# 07_LMS7002M_Power.net
KiCad netlist of a schematic drawn in Altium Designer
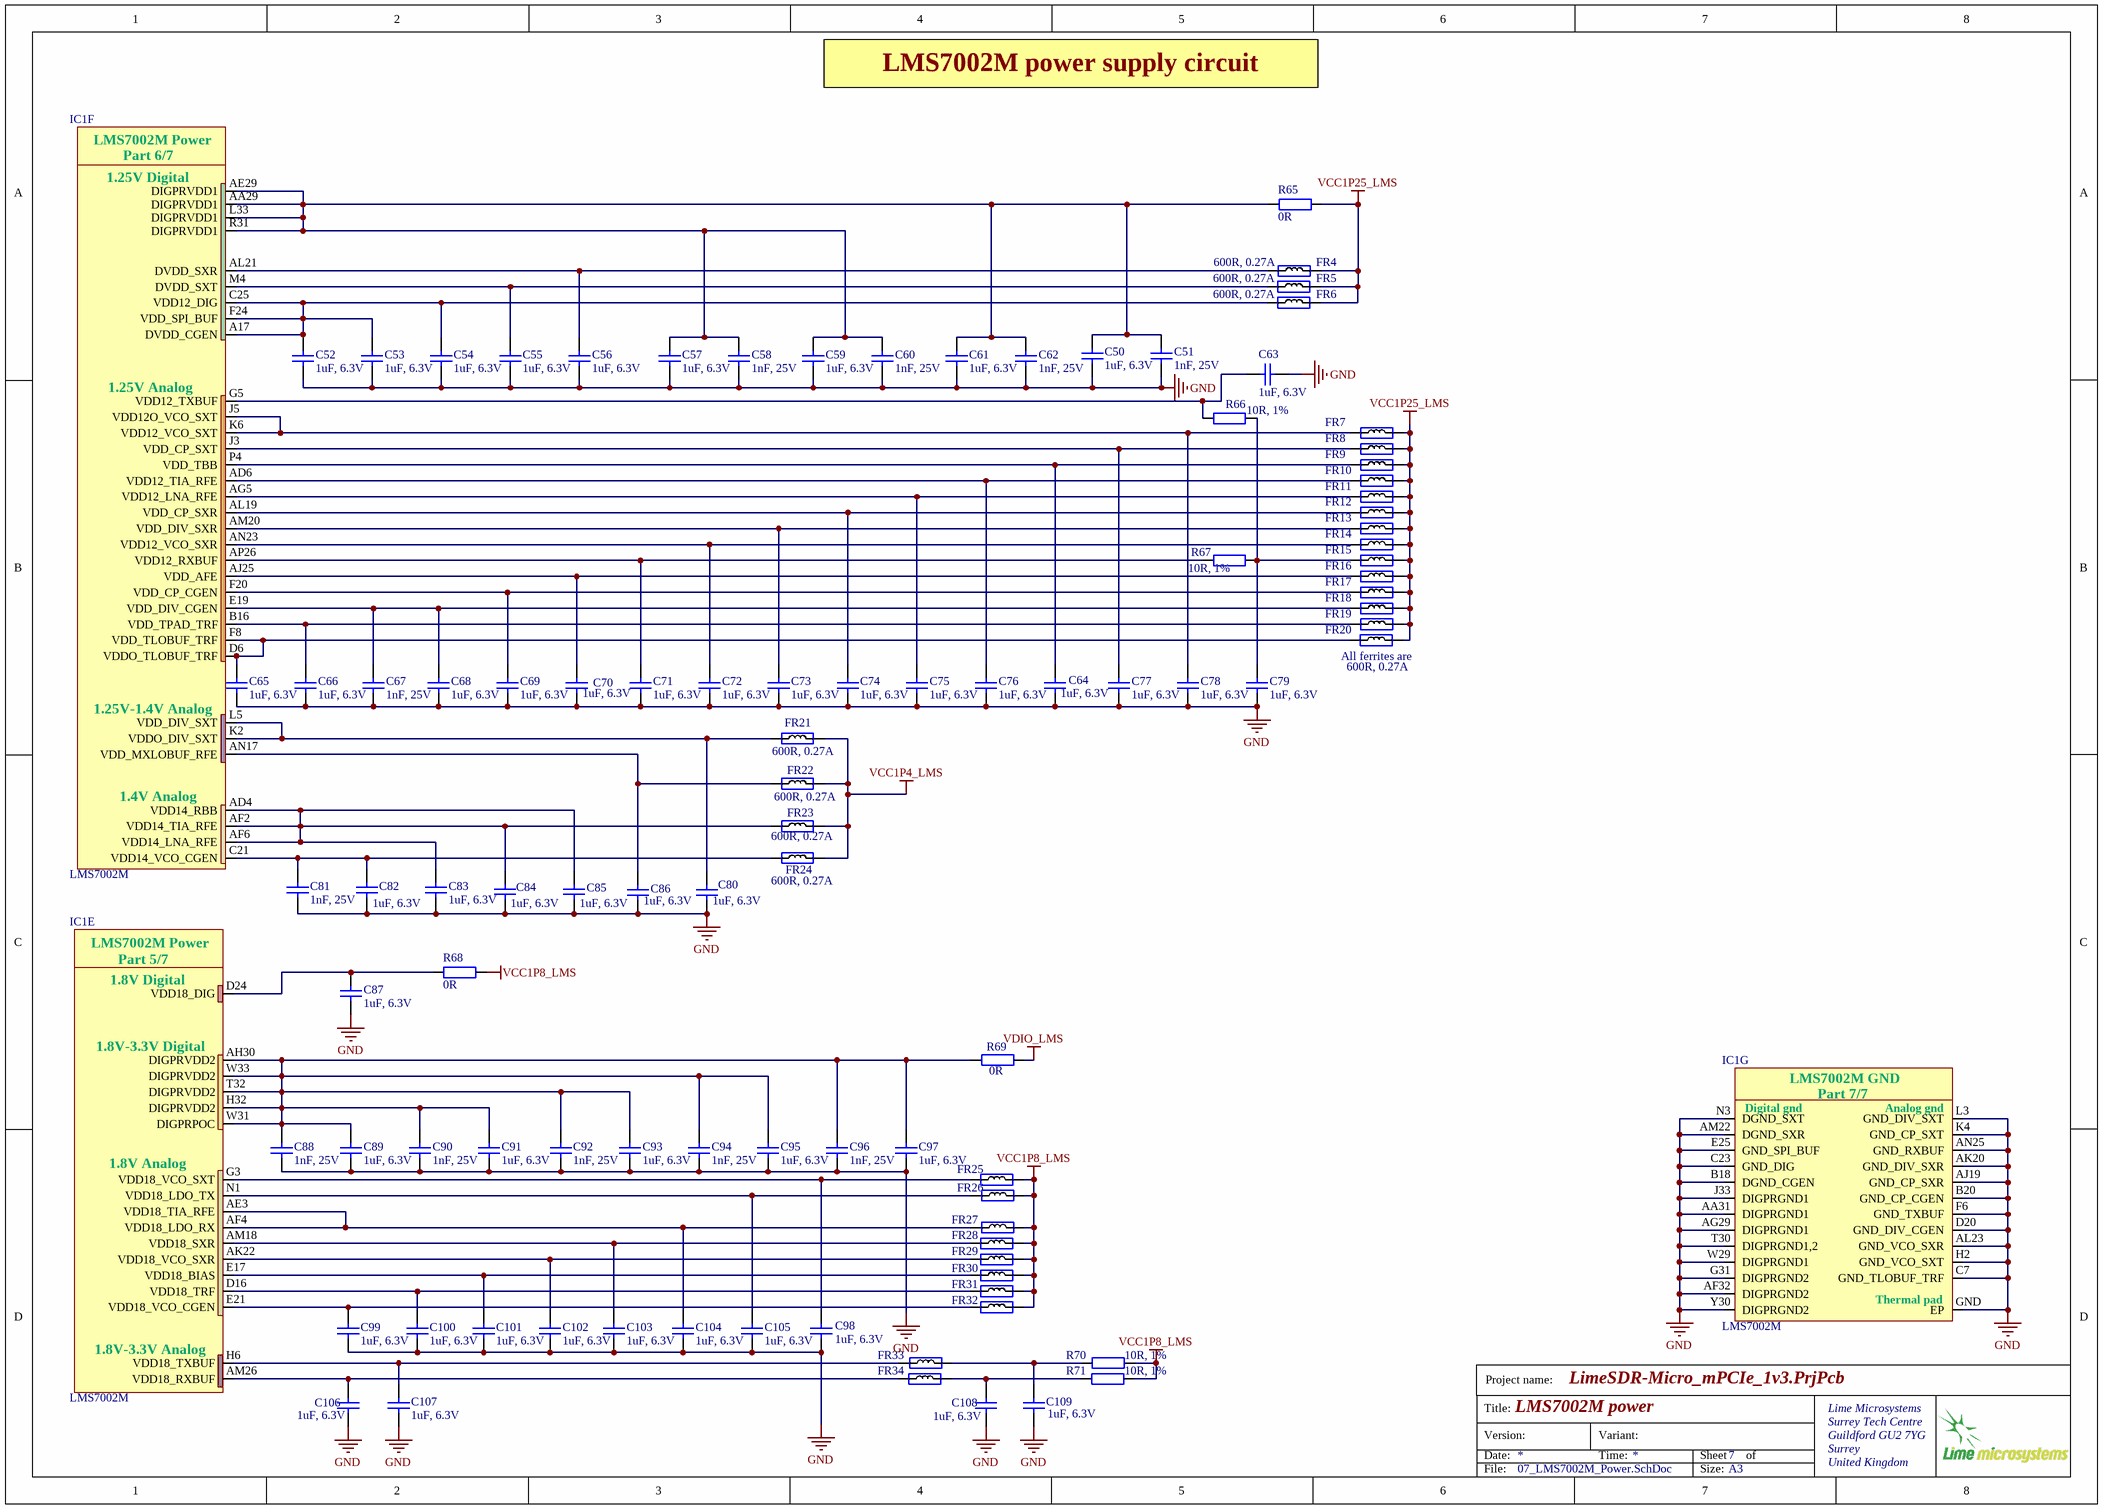
[diagram p0: 07_LMS7002M_Power.SchDoc]

(export (version "E")
  (design (tool "Eeschema 10.0.6"))
  (components
    (comp (ref "C50")
      (value "1uF, 6.3V")
      (footprint "CAP0201")
      (fields (field (name "TOLERANCE") "±20%") (field (name "MANUFACTURER") "TDK Corporation"))
      (libsource (lib "LimeMicroAltiumLib_schLib") (part "Cap_0402"))
    )
    (comp (ref "C51")
      (value "1nF, 25V")
      (footprint "CAP0201")
      (fields (field (name "TOLERANCE") "±10%") (field (name "MANUFACTURER") "TDK Corporation"))
      (libsource (lib "LimeMicroAltiumLib_schLib") (part "Cap_0402"))
    )
    (comp (ref "C52")
      (value "1uF, 6.3V")
      (footprint "CAP0201")
      (fields (field (name "TOLERANCE") "±20%") (field (name "MANUFACTURER") "TDK Corporation"))
      (libsource (lib "LimeMicroAltiumLib_schLib") (part "Cap_0402"))
    )
    (comp (ref "C53")
      (value "1uF, 6.3V")
      (footprint "CAP0201")
      (fields (field (name "TOLERANCE") "±20%") (field (name "MANUFACTURER") "TDK Corporation"))
      (libsource (lib "LimeMicroAltiumLib_schLib") (part "Cap_0402"))
    )
    (comp (ref "C54")
      (value "1uF, 6.3V")
      (footprint "CAP0201")
      (fields (field (name "TOLERANCE") "±20%") (field (name "MANUFACTURER") "TDK Corporation"))
      (libsource (lib "LimeMicroAltiumLib_schLib") (part "Cap_0402"))
    )
    (comp (ref "C55")
      (value "1uF, 6.3V")
      (footprint "CAP0201")
      (fields (field (name "TOLERANCE") "±20%") (field (name "MANUFACTURER") "TDK Corporation"))
      (libsource (lib "LimeMicroAltiumLib_schLib") (part "Cap_0402"))
    )
    (comp (ref "C56")
      (value "1uF, 6.3V")
      (footprint "CAP0201")
      (fields (field (name "TOLERANCE") "±20%") (field (name "MANUFACTURER") "TDK Corporation"))
      (libsource (lib "LimeMicroAltiumLib_schLib") (part "Cap_0402"))
    )
    (comp (ref "C57")
      (value "1uF, 6.3V")
      (footprint "CAP0201")
      (fields (field (name "TOLERANCE") "±20%") (field (name "MANUFACTURER") "TDK Corporation"))
      (libsource (lib "LimeMicroAltiumLib_schLib") (part "Cap_0402"))
    )
    (comp (ref "C58")
      (value "1nF, 25V")
      (footprint "CAP0201")
      (fields (field (name "TOLERANCE") "±10%") (field (name "MANUFACTURER") "TDK Corporation"))
      (libsource (lib "LimeMicroAltiumLib_schLib") (part "Cap_0402"))
    )
    (comp (ref "C59")
      (value "1uF, 6.3V")
      (footprint "CAP0201")
      (fields (field (name "TOLERANCE") "±20%") (field (name "MANUFACTURER") "TDK Corporation"))
      (libsource (lib "LimeMicroAltiumLib_schLib") (part "Cap_0402"))
    )
    (comp (ref "C60")
      (value "1nF, 25V")
      (footprint "CAP0201")
      (fields (field (name "TOLERANCE") "±10%") (field (name "MANUFACTURER") "TDK Corporation"))
      (libsource (lib "LimeMicroAltiumLib_schLib") (part "Cap_0402"))
    )
    (comp (ref "C61")
      (value "1uF, 6.3V")
      (footprint "CAP0201")
      (fields (field (name "TOLERANCE") "±20%") (field (name "MANUFACTURER") "TDK Corporation"))
      (libsource (lib "LimeMicroAltiumLib_schLib") (part "Cap_0402"))
    )
    (comp (ref "C62")
      (value "1nF, 25V")
      (footprint "CAP0201")
      (fields (field (name "TOLERANCE") "±10%") (field (name "MANUFACTURER") "TDK Corporation"))
      (libsource (lib "LimeMicroAltiumLib_schLib") (part "Cap_0402"))
    )
    (comp (ref "C63")
      (value "1uF, 6.3V")
      (footprint "CAP0201")
      (fields (field (name "TOLERANCE") "±20%") (field (name "MANUFACTURER") "TDK Corporation"))
      (libsource (lib "LimeMicroAltiumLib_schLib") (part "Cap_0402"))
    )
    (comp (ref "C64")
      (value "1uF, 6.3V")
      (footprint "CAP0201")
      (fields (field (name "TOLERANCE") "±20%") (field (name "MANUFACTURER") "TDK Corporation"))
      (libsource (lib "LimeMicroAltiumLib_schLib") (part "Cap_0402"))
    )
    (comp (ref "C65")
      (value "1uF, 6.3V")
      (footprint "CAP0201")
      (fields (field (name "TOLERANCE") "±20%") (field (name "MANUFACTURER") "TDK Corporation"))
      (libsource (lib "LimeMicroAltiumLib_schLib") (part "Cap_0402"))
    )
    (comp (ref "C66")
      (value "1uF, 6.3V")
      (footprint "CAP0201")
      (fields (field (name "TOLERANCE") "±20%") (field (name "MANUFACTURER") "TDK Corporation"))
      (libsource (lib "LimeMicroAltiumLib_schLib") (part "Cap_0402"))
    )
    (comp (ref "C67")
      (value "1nF, 25V")
      (footprint "CAP0201")
      (fields (field (name "TOLERANCE") "±10%") (field (name "MANUFACTURER") "TDK Corporation"))
      (libsource (lib "LimeMicroAltiumLib_schLib") (part "Cap_0402"))
    )
    (comp (ref "C68")
      (value "1uF, 6.3V")
      (footprint "CAP0201")
      (fields (field (name "TOLERANCE") "±20%") (field (name "MANUFACTURER") "TDK Corporation"))
      (libsource (lib "LimeMicroAltiumLib_schLib") (part "Cap_0402"))
    )
    (comp (ref "C69")
      (value "1uF, 6.3V")
      (footprint "CAP0201")
      (fields (field (name "TOLERANCE") "±20%") (field (name "MANUFACTURER") "TDK Corporation"))
      (libsource (lib "LimeMicroAltiumLib_schLib") (part "Cap_0402"))
    )
    (comp (ref "C70")
      (value "1uF, 6.3V")
      (footprint "CAP0201")
      (fields (field (name "TOLERANCE") "±20%") (field (name "MANUFACTURER") "TDK Corporation"))
      (libsource (lib "LimeMicroAltiumLib_schLib") (part "Cap_0402"))
    )
    (comp (ref "C71")
      (value "1uF, 6.3V")
      (footprint "CAP0201")
      (fields (field (name "TOLERANCE") "±20%") (field (name "MANUFACTURER") "TDK Corporation"))
      (libsource (lib "LimeMicroAltiumLib_schLib") (part "Cap_0402"))
    )
    (comp (ref "C72")
      (value "1uF, 6.3V")
      (footprint "CAP0201")
      (fields (field (name "TOLERANCE") "±20%") (field (name "MANUFACTURER") "TDK Corporation"))
      (libsource (lib "LimeMicroAltiumLib_schLib") (part "Cap_0402"))
    )
    (comp (ref "C73")
      (value "1uF, 6.3V")
      (footprint "CAP0201")
      (fields (field (name "TOLERANCE") "±20%") (field (name "MANUFACTURER") "TDK Corporation"))
      (libsource (lib "LimeMicroAltiumLib_schLib") (part "Cap_0402"))
    )
    (comp (ref "C74")
      (value "1uF, 6.3V")
      (footprint "CAP0201")
      (fields (field (name "TOLERANCE") "±20%") (field (name "MANUFACTURER") "TDK Corporation"))
      (libsource (lib "LimeMicroAltiumLib_schLib") (part "Cap_0402"))
    )
    (comp (ref "C75")
      (value "1uF, 6.3V")
      (footprint "CAP0201")
      (fields (field (name "TOLERANCE") "±20%") (field (name "MANUFACTURER") "TDK Corporation"))
      (libsource (lib "LimeMicroAltiumLib_schLib") (part "Cap_0402"))
    )
    (comp (ref "C76")
      (value "1uF, 6.3V")
      (footprint "CAP0201")
      (fields (field (name "TOLERANCE") "±20%") (field (name "MANUFACTURER") "TDK Corporation"))
      (libsource (lib "LimeMicroAltiumLib_schLib") (part "Cap_0402"))
    )
    (comp (ref "C77")
      (value "1uF, 6.3V")
      (footprint "CAP0201")
      (fields (field (name "TOLERANCE") "±20%") (field (name "MANUFACTURER") "TDK Corporation"))
      (libsource (lib "LimeMicroAltiumLib_schLib") (part "Cap_0402"))
    )
    (comp (ref "C78")
      (value "1uF, 6.3V")
      (footprint "CAP0201")
      (fields (field (name "TOLERANCE") "±20%") (field (name "MANUFACTURER") "TDK Corporation"))
      (libsource (lib "LimeMicroAltiumLib_schLib") (part "Cap_0402"))
    )
    (comp (ref "C79")
      (value "1uF, 6.3V")
      (footprint "CAP0201")
      (fields (field (name "TOLERANCE") "±20%") (field (name "MANUFACTURER") "TDK Corporation"))
      (libsource (lib "LimeMicroAltiumLib_schLib") (part "Cap_0402"))
    )
    (comp (ref "C80")
      (value "1uF, 6.3V")
      (footprint "CAP0201")
      (fields (field (name "TOLERANCE") "±20%") (field (name "MANUFACTURER") "TDK Corporation"))
      (libsource (lib "LimeMicroAltiumLib_schLib") (part "Cap_0402"))
    )
    (comp (ref "C81")
      (value "1nF, 25V")
      (footprint "CAP0201")
      (fields (field (name "TOLERANCE") "±10%") (field (name "MANUFACTURER") "TDK Corporation"))
      (libsource (lib "LimeMicroAltiumLib_schLib") (part "Cap_0402"))
    )
    (comp (ref "C82")
      (value "1uF, 6.3V")
      (footprint "CAP0201")
      (fields (field (name "TOLERANCE") "±20%") (field (name "MANUFACTURER") "TDK Corporation"))
      (libsource (lib "LimeMicroAltiumLib_schLib") (part "Cap_0402"))
    )
    (comp (ref "C83")
      (value "1uF, 6.3V")
      (footprint "CAP0201")
      (fields (field (name "TOLERANCE") "±20%") (field (name "MANUFACTURER") "TDK Corporation"))
      (libsource (lib "LimeMicroAltiumLib_schLib") (part "Cap_0402"))
    )
    (comp (ref "C84")
      (value "1uF, 6.3V")
      (footprint "CAP0201")
      (fields (field (name "TOLERANCE") "±20%") (field (name "MANUFACTURER") "TDK Corporation"))
      (libsource (lib "LimeMicroAltiumLib_schLib") (part "Cap_0402"))
    )
    (comp (ref "C85")
      (value "1uF, 6.3V")
      (footprint "CAP0201")
      (fields (field (name "TOLERANCE") "±20%") (field (name "MANUFACTURER") "TDK Corporation"))
      (libsource (lib "LimeMicroAltiumLib_schLib") (part "Cap_0402"))
    )
    (comp (ref "C86")
      (value "1uF, 6.3V")
      (footprint "CAP0201")
      (fields (field (name "TOLERANCE") "±20%") (field (name "MANUFACTURER") "TDK Corporation"))
      (libsource (lib "LimeMicroAltiumLib_schLib") (part "Cap_0402"))
    )
    (comp (ref "C87")
      (value "1uF, 6.3V")
      (footprint "CAP0201")
      (fields (field (name "TOLERANCE") "±20%") (field (name "MANUFACTURER") "TDK Corporation"))
      (libsource (lib "LimeMicroAltiumLib_schLib") (part "Cap_0402"))
    )
    (comp (ref "C88")
      (value "1nF, 25V")
      (footprint "CAP0201")
      (fields (field (name "TOLERANCE") "±10%") (field (name "MANUFACTURER") "TDK Corporation"))
      (libsource (lib "LimeMicroAltiumLib_schLib") (part "Cap_0402"))
    )
    (comp (ref "C89")
      (value "1uF, 6.3V")
      (footprint "CAP0201")
      (fields (field (name "TOLERANCE") "±20%") (field (name "MANUFACTURER") "TDK Corporation"))
      (libsource (lib "LimeMicroAltiumLib_schLib") (part "Cap_0402"))
    )
    (comp (ref "C90")
      (value "1nF, 25V")
      (footprint "CAP0201")
      (fields (field (name "TOLERANCE") "±10%") (field (name "MANUFACTURER") "TDK Corporation"))
      (libsource (lib "LimeMicroAltiumLib_schLib") (part "Cap_0402"))
    )
    (comp (ref "C91")
      (value "1uF, 6.3V")
      (footprint "CAP0201")
      (fields (field (name "TOLERANCE") "±20%") (field (name "MANUFACTURER") "TDK Corporation"))
      (libsource (lib "LimeMicroAltiumLib_schLib") (part "Cap_0402"))
    )
    (comp (ref "C92")
      (value "1nF, 25V")
      (footprint "CAP0201")
      (fields (field (name "TOLERANCE") "±10%") (field (name "MANUFACTURER") "TDK Corporation"))
      (libsource (lib "LimeMicroAltiumLib_schLib") (part "Cap_0402"))
    )
    (comp (ref "C93")
      (value "1uF, 6.3V")
      (footprint "CAP0201")
      (fields (field (name "TOLERANCE") "±20%") (field (name "MANUFACTURER") "TDK Corporation"))
      (libsource (lib "LimeMicroAltiumLib_schLib") (part "Cap_0402"))
    )
    (comp (ref "C94")
      (value "1nF, 25V")
      (footprint "CAP0201")
      (fields (field (name "TOLERANCE") "±10%") (field (name "MANUFACTURER") "TDK Corporation"))
      (libsource (lib "LimeMicroAltiumLib_schLib") (part "Cap_0402"))
    )
    (comp (ref "C95")
      (value "1uF, 6.3V")
      (footprint "CAP0201")
      (fields (field (name "TOLERANCE") "±20%") (field (name "MANUFACTURER") "TDK Corporation"))
      (libsource (lib "LimeMicroAltiumLib_schLib") (part "Cap_0402"))
    )
    (comp (ref "C96")
      (value "1nF, 25V")
      (footprint "CAP0201")
      (fields (field (name "TOLERANCE") "±10%") (field (name "MANUFACTURER") "TDK Corporation"))
      (libsource (lib "LimeMicroAltiumLib_schLib") (part "Cap_0402"))
    )
    (comp (ref "C97")
      (value "1uF, 6.3V")
      (footprint "CAP0201")
      (fields (field (name "TOLERANCE") "±20%") (field (name "MANUFACTURER") "TDK Corporation"))
      (libsource (lib "LimeMicroAltiumLib_schLib") (part "Cap_0402"))
    )
    (comp (ref "C98")
      (value "1uF, 6.3V")
      (footprint "CAP0201")
      (fields (field (name "TOLERANCE") "±20%") (field (name "MANUFACTURER") "TDK Corporation"))
      (libsource (lib "LimeMicroAltiumLib_schLib") (part "Cap_0402"))
    )
    (comp (ref "C99")
      (value "1uF, 6.3V")
      (footprint "CAP0201")
      (fields (field (name "TOLERANCE") "±20%") (field (name "MANUFACTURER") "TDK Corporation"))
      (libsource (lib "LimeMicroAltiumLib_schLib") (part "Cap_0402"))
    )
    (comp (ref "C100")
      (value "1uF, 6.3V")
      (footprint "CAP0201")
      (fields (field (name "TOLERANCE") "±20%") (field (name "MANUFACTURER") "TDK Corporation"))
      (libsource (lib "LimeMicroAltiumLib_schLib") (part "Cap_0402"))
    )
    (comp (ref "C101")
      (value "1uF, 6.3V")
      (footprint "CAP0201")
      (fields (field (name "TOLERANCE") "±20%") (field (name "MANUFACTURER") "TDK Corporation"))
      (libsource (lib "LimeMicroAltiumLib_schLib") (part "Cap_0402"))
    )
    (comp (ref "C102")
      (value "1uF, 6.3V")
      (footprint "CAP0201")
      (fields (field (name "TOLERANCE") "±20%") (field (name "MANUFACTURER") "TDK Corporation"))
      (libsource (lib "LimeMicroAltiumLib_schLib") (part "Cap_0402"))
    )
    (comp (ref "C103")
      (value "1uF, 6.3V")
      (footprint "CAP0201")
      (fields (field (name "TOLERANCE") "±20%") (field (name "MANUFACTURER") "TDK Corporation"))
      (libsource (lib "LimeMicroAltiumLib_schLib") (part "Cap_0402"))
    )
    (comp (ref "C104")
      (value "1uF, 6.3V")
      (footprint "CAP0201")
      (fields (field (name "TOLERANCE") "±20%") (field (name "MANUFACTURER") "TDK Corporation"))
      (libsource (lib "LimeMicroAltiumLib_schLib") (part "Cap_0402"))
    )
    (comp (ref "C105")
      (value "1uF, 6.3V")
      (footprint "CAP0201")
      (fields (field (name "TOLERANCE") "±20%") (field (name "MANUFACTURER") "TDK Corporation"))
      (libsource (lib "LimeMicroAltiumLib_schLib") (part "Cap_0402"))
    )
    (comp (ref "C106")
      (value "1uF, 6.3V")
      (footprint "CAP0201")
      (fields (field (name "TOLERANCE") "±20%") (field (name "MANUFACTURER") "TDK Corporation"))
      (libsource (lib "LimeMicroAltiumLib_schLib") (part "Cap_0402"))
    )
    (comp (ref "C107")
      (value "1uF, 6.3V")
      (footprint "CAP0201")
      (fields (field (name "TOLERANCE") "±20%") (field (name "MANUFACTURER") "TDK Corporation"))
      (libsource (lib "LimeMicroAltiumLib_schLib") (part "Cap_0402"))
    )
    (comp (ref "C108")
      (value "1uF, 6.3V")
      (footprint "CAP0201")
      (fields (field (name "TOLERANCE") "±20%") (field (name "MANUFACTURER") "TDK Corporation"))
      (libsource (lib "LimeMicroAltiumLib_schLib") (part "Cap_0402"))
    )
    (comp (ref "C109")
      (value "1uF, 6.3V")
      (footprint "CAP0201")
      (fields (field (name "TOLERANCE") "±20%") (field (name "MANUFACTURER") "TDK Corporation"))
      (libsource (lib "LimeMicroAltiumLib_schLib") (part "Cap_0402"))
    )
    (comp (ref "FR4")
      (value "600R, 0.27A")
      (footprint "RES0201")
      (fields (field (name "MANUFACTURER") "Taiyo Yuden"))
      (libsource (lib "LimeMicroAltiumLib_schLib") (part "Ferrite"))
    )
    (comp (ref "FR5")
      (value "600R, 0.27A")
      (footprint "RES0201")
      (fields (field (name "MANUFACTURER") "Taiyo Yuden"))
      (libsource (lib "LimeMicroAltiumLib_schLib") (part "Ferrite"))
    )
    (comp (ref "FR6")
      (value "600R, 0.27A")
      (footprint "RES0201")
      (fields (field (name "MANUFACTURER") "Taiyo Yuden"))
      (libsource (lib "LimeMicroAltiumLib_schLib") (part "Ferrite"))
    )
    (comp (ref "FR7")
      (value "600R, 0.27A")
      (footprint "RES0201")
      (fields (field (name "MANUFACTURER") "Taiyo Yuden"))
      (libsource (lib "LimeMicroAltiumLib_schLib") (part "Ferrite"))
    )
    (comp (ref "FR8")
      (value "600R, 0.27A")
      (footprint "RES0201")
      (fields (field (name "MANUFACTURER") "Taiyo Yuden"))
      (libsource (lib "LimeMicroAltiumLib_schLib") (part "Ferrite"))
    )
    (comp (ref "FR9")
      (value "600R, 0.27A")
      (footprint "RES0201")
      (fields (field (name "MANUFACTURER") "Taiyo Yuden"))
      (libsource (lib "LimeMicroAltiumLib_schLib") (part "Ferrite"))
    )
    (comp (ref "FR10")
      (value "600R, 0.27A")
      (footprint "RES0201")
      (fields (field (name "MANUFACTURER") "Taiyo Yuden"))
      (libsource (lib "LimeMicroAltiumLib_schLib") (part "Ferrite"))
    )
    (comp (ref "FR11")
      (value "600R, 0.27A")
      (footprint "RES0201")
      (fields (field (name "MANUFACTURER") "Taiyo Yuden"))
      (libsource (lib "LimeMicroAltiumLib_schLib") (part "Ferrite"))
    )
    (comp (ref "FR12")
      (value "600R, 0.27A")
      (footprint "RES0201")
      (fields (field (name "MANUFACTURER") "Taiyo Yuden"))
      (libsource (lib "LimeMicroAltiumLib_schLib") (part "Ferrite"))
    )
    (comp (ref "FR13")
      (value "600R, 0.27A")
      (footprint "RES0201")
      (fields (field (name "MANUFACTURER") "Taiyo Yuden"))
      (libsource (lib "LimeMicroAltiumLib_schLib") (part "Ferrite"))
    )
    (comp (ref "FR14")
      (value "600R, 0.27A")
      (footprint "RES0201")
      (fields (field (name "MANUFACTURER") "Taiyo Yuden"))
      (libsource (lib "LimeMicroAltiumLib_schLib") (part "Ferrite"))
    )
    (comp (ref "FR15")
      (value "600R, 0.27A")
      (footprint "RES0201")
      (fields (field (name "MANUFACTURER") "Taiyo Yuden"))
      (libsource (lib "LimeMicroAltiumLib_schLib") (part "Ferrite"))
    )
    (comp (ref "FR16")
      (value "600R, 0.27A")
      (footprint "RES0201")
      (fields (field (name "MANUFACTURER") "Taiyo Yuden"))
      (libsource (lib "LimeMicroAltiumLib_schLib") (part "Ferrite"))
    )
    (comp (ref "FR17")
      (value "600R, 0.27A")
      (footprint "RES0201")
      (fields (field (name "MANUFACTURER") "Taiyo Yuden"))
      (libsource (lib "LimeMicroAltiumLib_schLib") (part "Ferrite"))
    )
    (comp (ref "FR18")
      (value "600R, 0.27A")
      (footprint "RES0201")
      (fields (field (name "MANUFACTURER") "Taiyo Yuden"))
      (libsource (lib "LimeMicroAltiumLib_schLib") (part "Ferrite"))
    )
    (comp (ref "FR19")
      (value "600R, 0.27A")
      (footprint "RES0201")
      (fields (field (name "MANUFACTURER") "Taiyo Yuden"))
      (libsource (lib "LimeMicroAltiumLib_schLib") (part "Ferrite"))
    )
    (comp (ref "FR20")
      (value "600R, 0.27A")
      (footprint "RES0201")
      (fields (field (name "MANUFACTURER") "Taiyo Yuden"))
      (libsource (lib "LimeMicroAltiumLib_schLib") (part "Ferrite"))
    )
    (comp (ref "FR21")
      (value "600R, 0.27A")
      (footprint "RES0201")
      (fields (field (name "MANUFACTURER") "Taiyo Yuden"))
      (libsource (lib "LimeMicroAltiumLib_schLib") (part "Ferrite"))
    )
    (comp (ref "FR22")
      (value "600R, 0.27A")
      (footprint "RES0201")
      (fields (field (name "MANUFACTURER") "Taiyo Yuden"))
      (libsource (lib "LimeMicroAltiumLib_schLib") (part "Ferrite"))
    )
    (comp (ref "FR23")
      (value "600R, 0.27A")
      (footprint "RES0201")
      (fields (field (name "MANUFACTURER") "Taiyo Yuden"))
      (libsource (lib "LimeMicroAltiumLib_schLib") (part "Ferrite"))
    )
    (comp (ref "FR24")
      (value "600R, 0.27A")
      (footprint "RES0201")
      (fields (field (name "MANUFACTURER") "Taiyo Yuden"))
      (libsource (lib "LimeMicroAltiumLib_schLib") (part "Ferrite"))
    )
    (comp (ref "FR25")
      (value "600R, 0.27A")
      (footprint "RES0201")
      (fields (field (name "MANUFACTURER") "Taiyo Yuden"))
      (libsource (lib "LimeMicroAltiumLib_schLib") (part "Ferrite"))
    )
    (comp (ref "FR26")
      (value "600R, 0.27A")
      (footprint "RES0201")
      (fields (field (name "MANUFACTURER") "Taiyo Yuden"))
      (libsource (lib "") (part "Ferrite_1"))
    )
    (comp (ref "FR27")
      (value "600R, 0.27A")
      (footprint "RES0201")
      (fields (field (name "MANUFACTURER") "Taiyo Yuden"))
      (libsource (lib "") (part "Ferrite_1"))
    )
    (comp (ref "FR28")
      (value "600R, 0.27A")
      (footprint "RES0201")
      (fields (field (name "MANUFACTURER") "Taiyo Yuden"))
      (libsource (lib "LimeMicroAltiumLib_schLib") (part "Ferrite"))
    )
    (comp (ref "FR29")
      (value "600R, 0.27A")
      (footprint "RES0201")
      (fields (field (name "MANUFACTURER") "Taiyo Yuden"))
      (libsource (lib "LimeMicroAltiumLib_schLib") (part "Ferrite"))
    )
    (comp (ref "FR30")
      (value "600R, 0.27A")
      (footprint "RES0201")
      (fields (field (name "MANUFACTURER") "Taiyo Yuden"))
      (libsource (lib "LimeMicroAltiumLib_schLib") (part "Ferrite"))
    )
    (comp (ref "FR31")
      (value "600R, 0.27A")
      (footprint "RES0201")
      (fields (field (name "MANUFACTURER") "Taiyo Yuden"))
      (libsource (lib "LimeMicroAltiumLib_schLib") (part "Ferrite"))
    )
    (comp (ref "FR32")
      (value "600R, 0.27A")
      (footprint "RES0201")
      (fields (field (name "MANUFACTURER") "Taiyo Yuden"))
      (libsource (lib "LimeMicroAltiumLib_schLib") (part "Ferrite"))
    )
    (comp (ref "FR33")
      (value "600R, 0.27A")
      (footprint "RES0201")
      (fields (field (name "MANUFACTURER") "Taiyo Yuden"))
      (libsource (lib "") (part "Ferrite_1"))
    )
    (comp (ref "FR34")
      (value "600R, 0.27A")
      (footprint "RES0201")
      (fields (field (name "MANUFACTURER") "Taiyo Yuden"))
      (libsource (lib "LimeMicroAltiumLib_schLib") (part "Ferrite"))
    )
    (comp (ref "IC1")
      (value "LMS7002M")
      (footprint "LMS7002M_v5_LESS_SILK")
      (description "Schematic symbol revision 4. Default footprint - 0.31mm pad")
      (fields (field (name "MANUFACTURER") "Lime Microsystems"))
      (libsource (lib "LimeMicroAltiumLib_schLib_r04") (part "LMS7002Mr4"))
    )
    (comp (ref "R65")
      (value "0R")
      (footprint "RES0402")
      (fields (field (name "MANUFACTURER") "Yageo") (field (name "TOLERANCE") "Jumper"))
      (libsource (lib "LimeMicroAltiumLib_schLib") (part "Res_0402"))
    )
    (comp (ref "R66")
      (value "10R, 1%")
      (footprint "RES0201")
      (fields
        (field (name "MANUFACTURER") "Panasonic Electronic Components")
        (field (name "TOLERANCE") "±1%")
      )
      (libsource (lib "LimeMicroAltiumLib_schLib") (part "Res_0402"))
    )
    (comp (ref "R67")
      (value "10R, 1%")
      (footprint "RES0201")
      (fields
        (field (name "MANUFACTURER") "Panasonic Electronic Components")
        (field (name "TOLERANCE") "±1%")
      )
      (libsource (lib "LimeMicroAltiumLib_schLib") (part "Res_0402"))
    )
    (comp (ref "R68")
      (value "0R")
      (footprint "RES0201")
      (fields (field (name "MANUFACTURER") "Yageo") (field (name "TOLERANCE") "5%"))
      (libsource (lib "LimeMicroAltiumLib_schLib") (part "Res_0402"))
    )
    (comp (ref "R69")
      (value "0R")
      (footprint "RES0402")
      (fields (field (name "MANUFACTURER") "Yageo") (field (name "TOLERANCE") "Jumper"))
      (libsource (lib "LimeMicroAltiumLib_schLib") (part "Res_0402"))
    )
    (comp (ref "R70")
      (value "10R, 1%")
      (footprint "RES0201")
      (fields
        (field (name "MANUFACTURER") "Panasonic Electronic Components")
        (field (name "TOLERANCE") "±1%")
      )
      (libsource (lib "LimeMicroAltiumLib_schLib") (part "Res_0402"))
    )
    (comp (ref "R71")
      (value "10R, 1%")
      (footprint "RES0201")
      (fields
        (field (name "MANUFACTURER") "Panasonic Electronic Components")
        (field (name "TOLERANCE") "±1%")
      )
      (libsource (lib "LimeMicroAltiumLib_schLib") (part "Res_0402"))
    )
  )
  (nets
    (net (code "1") (name "GND") (class "Default")
      (node (ref "C100") (pin "2") (pinfunction "2_2") (pintype "passive"))
      (node (ref "C101") (pin "2") (pinfunction "2_2") (pintype "passive"))
      (node (ref "C102") (pin "2") (pinfunction "2_2") (pintype "passive"))
      (node (ref "C103") (pin "2") (pinfunction "2_2") (pintype "passive"))
      (node (ref "C104") (pin "2") (pinfunction "2_2") (pintype "passive"))
      (node (ref "C105") (pin "2") (pinfunction "2_2") (pintype "passive"))
      (node (ref "C106") (pin "2") (pinfunction "2_2") (pintype "passive"))
      (node (ref "C107") (pin "2") (pinfunction "2_2") (pintype "passive"))
      (node (ref "C108") (pin "2") (pinfunction "2_2") (pintype "passive"))
      (node (ref "C109") (pin "2") (pinfunction "2_2") (pintype "passive"))
      (node (ref "C50") (pin "2") (pinfunction "2_2") (pintype "passive"))
      (node (ref "C51") (pin "2") (pinfunction "2_2") (pintype "passive"))
      (node (ref "C52") (pin "2") (pinfunction "2_2") (pintype "passive"))
      (node (ref "C53") (pin "2") (pinfunction "2_2") (pintype "passive"))
      (node (ref "C54") (pin "2") (pinfunction "2_2") (pintype "passive"))
      (node (ref "C55") (pin "1") (pinfunction "1_1") (pintype "passive"))
      (node (ref "C56") (pin "2") (pinfunction "2_2") (pintype "passive"))
      (node (ref "C57") (pin "2") (pinfunction "2_2") (pintype "passive"))
      (node (ref "C58") (pin "2") (pinfunction "2_2") (pintype "passive"))
      (node (ref "C59") (pin "2") (pinfunction "2_2") (pintype "passive"))
      (node (ref "C60") (pin "2") (pinfunction "2_2") (pintype "passive"))
      (node (ref "C61") (pin "2") (pinfunction "2_2") (pintype "passive"))
      (node (ref "C62") (pin "2") (pinfunction "2_2") (pintype "passive"))
      (node (ref "C63") (pin "2") (pinfunction "2_2") (pintype "passive"))
      (node (ref "C64") (pin "2") (pinfunction "2_2") (pintype "passive"))
      (node (ref "C65") (pin "2") (pinfunction "2_2") (pintype "passive"))
      (node (ref "C66") (pin "2") (pinfunction "2_2") (pintype "passive"))
      (node (ref "C67") (pin "2") (pinfunction "2_2") (pintype "passive"))
      (node (ref "C68") (pin "2") (pinfunction "2_2") (pintype "passive"))
      (node (ref "C69") (pin "1") (pinfunction "1_1") (pintype "passive"))
      (node (ref "C70") (pin "2") (pinfunction "2_2") (pintype "passive"))
      (node (ref "C71") (pin "2") (pinfunction "2_2") (pintype "passive"))
      (node (ref "C72") (pin "2") (pinfunction "2_2") (pintype "passive"))
      (node (ref "C73") (pin "2") (pinfunction "2_2") (pintype "passive"))
      (node (ref "C74") (pin "2") (pinfunction "2_2") (pintype "passive"))
      (node (ref "C75") (pin "2") (pinfunction "2_2") (pintype "passive"))
      (node (ref "C76") (pin "1") (pinfunction "1_1") (pintype "passive"))
      (node (ref "C77") (pin "2") (pinfunction "2_2") (pintype "passive"))
      (node (ref "C78") (pin "1") (pinfunction "1_1") (pintype "passive"))
      (node (ref "C79") (pin "1") (pinfunction "1_1") (pintype "passive"))
      (node (ref "C80") (pin "2") (pinfunction "2_2") (pintype "passive"))
      (node (ref "C81") (pin "2") (pinfunction "2_2") (pintype "passive"))
      (node (ref "C82") (pin "2") (pinfunction "2_2") (pintype "passive"))
      (node (ref "C83") (pin "2") (pinfunction "2_2") (pintype "passive"))
      (node (ref "C84") (pin "2") (pinfunction "2_2") (pintype "passive"))
      (node (ref "C85") (pin "2") (pinfunction "2_2") (pintype "passive"))
      (node (ref "C86") (pin "2") (pinfunction "2_2") (pintype "passive"))
      (node (ref "C87") (pin "2") (pinfunction "2_2") (pintype "passive"))
      (node (ref "C88") (pin "2") (pinfunction "2_2") (pintype "passive"))
      (node (ref "C89") (pin "2") (pinfunction "2_2") (pintype "passive"))
      (node (ref "C90") (pin "2") (pinfunction "2_2") (pintype "passive"))
      (node (ref "C91") (pin "2") (pinfunction "2_2") (pintype "passive"))
      (node (ref "C92") (pin "2") (pinfunction "2_2") (pintype "passive"))
      (node (ref "C93") (pin "2") (pinfunction "2_2") (pintype "passive"))
      (node (ref "C94") (pin "2") (pinfunction "2_2") (pintype "passive"))
      (node (ref "C95") (pin "2") (pinfunction "2_2") (pintype "passive"))
      (node (ref "C96") (pin "2") (pinfunction "2_2") (pintype "passive"))
      (node (ref "C97") (pin "2") (pinfunction "2_2") (pintype "passive"))
      (node (ref "C98") (pin "2") (pinfunction "2_2") (pintype "passive"))
      (node (ref "C99") (pin "2") (pinfunction "2_2") (pintype "passive"))
      (node (ref "IC1") (pin "AA31") (pinfunction "DIGPRGND1_AA31") (pintype "passive"))
      (node (ref "IC1") (pin "AF32") (pinfunction "DIGPRGND2_AF32") (pintype "passive"))
      (node (ref "IC1") (pin "AG29") (pinfunction "DIGPRGND1_AG29") (pintype "passive"))
      (node (ref "IC1") (pin "AJ19") (pinfunction "GND_CP_SXR_AJ19") (pintype "passive"))
      (node (ref "IC1") (pin "AK20") (pinfunction "GND_DIV_SXR_AK20") (pintype "passive"))
      (node (ref "IC1") (pin "AL23") (pinfunction "GND_VCO_SXR_AL23") (pintype "passive"))
      (node (ref "IC1") (pin "AM22") (pinfunction "DGND_SXR_AM22") (pintype "passive"))
      (node (ref "IC1") (pin "AN25") (pinfunction "GND_RXBUF_AN25") (pintype "passive"))
      (node (ref "IC1") (pin "B18") (pinfunction "DGND_CGEN_B18") (pintype "passive"))
      (node (ref "IC1") (pin "B20") (pinfunction "GND_CP_CGEN_B20") (pintype "passive"))
      (node (ref "IC1") (pin "C23") (pinfunction "GND_DIG_C23") (pintype "passive"))
      (node (ref "IC1") (pin "C7") (pinfunction "GND_TLOBUF_TRF_C7") (pintype "passive"))
      (node (ref "IC1") (pin "D20") (pinfunction "GND_DIV_CGEN_D20") (pintype "passive"))
      (node (ref "IC1") (pin "E25") (pinfunction "GND_SPI_BUF_E25") (pintype "passive"))
      (node (ref "IC1") (pin "F6") (pinfunction "GND_TXBUF_F6") (pintype "passive"))
      (node (ref "IC1") (pin "G31") (pinfunction "DIGPRGND2_G31") (pintype "passive"))
      (node (ref "IC1") (pin "GND") (pinfunction "EP_GND") (pintype "passive"))
      (node (ref "IC1") (pin "H2") (pinfunction "GND_VCO_SXT_H2") (pintype "passive"))
      (node (ref "IC1") (pin "J33") (pinfunction "DIGPRGND1_J33") (pintype "passive"))
      (node (ref "IC1") (pin "K4") (pinfunction "GND_CP_SXT_K4") (pintype "passive"))
      (node (ref "IC1") (pin "L3") (pinfunction "GND_DIV_SXT_L3") (pintype "passive"))
      (node (ref "IC1") (pin "N3") (pinfunction "DGND_SXT_N3") (pintype "passive"))
      (node (ref "IC1") (pin "T30") (pinfunction "DIGPRGND1,2_T30") (pintype "passive"))
      (node (ref "IC1") (pin "W29") (pinfunction "DIGPRGND1_W29") (pintype "passive"))
      (node (ref "IC1") (pin "Y30") (pinfunction "DIGPRGND2_Y30") (pintype "passive"))
    )
    (net (code "2") (name "Net-(C50-Pad1)") (class "Default")
      (node (ref "C50") (pin "1") (pinfunction "1_1") (pintype "passive"))
      (node (ref "C51") (pin "1") (pinfunction "1_1") (pintype "passive"))
      (node (ref "C57") (pin "1") (pinfunction "1_1") (pintype "passive"))
      (node (ref "C58") (pin "1") (pinfunction "1_1") (pintype "passive"))
      (node (ref "C59") (pin "1") (pinfunction "1_1") (pintype "passive"))
      (node (ref "C60") (pin "1") (pinfunction "1_1") (pintype "passive"))
      (node (ref "C61") (pin "1") (pinfunction "1_1") (pintype "passive"))
      (node (ref "C62") (pin "1") (pinfunction "1_1") (pintype "passive"))
      (node (ref "IC1") (pin "AA29") (pinfunction "DIGPRVDD1_AA29") (pintype "power_in"))
      (node (ref "IC1") (pin "AE29") (pinfunction "DIGPRVDD1_AE29") (pintype "power_in"))
      (node (ref "IC1") (pin "L33") (pinfunction "DIGPRVDD1_L33") (pintype "power_in"))
      (node (ref "IC1") (pin "R31") (pinfunction "DIGPRVDD1_R31") (pintype "power_in"))
      (node (ref "R65") (pin "2") (pinfunction "2_2") (pintype "passive"))
    )
    (net (code "3") (name "Net-(C79-Pad2)") (class "Default")
      (node (ref "C79") (pin "2") (pinfunction "2_2") (pintype "passive"))
      (node (ref "FR15") (pin "1") (pinfunction "1_1") (pintype "passive"))
      (node (ref "R66") (pin "2") (pinfunction "2_2") (pintype "passive"))
      (node (ref "R67") (pin "2") (pinfunction "2_2") (pintype "passive"))
    )
    (net (code "4") (name "Net-(C108-Pad1)") (class "Default")
      (node (ref "C108") (pin "1") (pinfunction "1_1") (pintype "passive"))
      (node (ref "FR34") (pin "2") (pinfunction "2_2") (pintype "passive"))
      (node (ref "R71") (pin "2") (pinfunction "2_2") (pintype "passive"))
    )
    (net (code "5") (name "Net-(C109-Pad1)") (class "Default")
      (node (ref "C109") (pin "1") (pinfunction "1_1") (pintype "passive"))
      (node (ref "FR33") (pin "1") (pinfunction "1_1") (pintype "passive"))
      (node (ref "R70") (pin "1") (pinfunction "1_1") (pintype "passive"))
    )
    (net (code "6") (name "Net-(IC1E-DIGPRPOC)") (class "Default")
      (node (ref "C88") (pin "1") (pinfunction "1_1") (pintype "passive"))
      (node (ref "C89") (pin "1") (pinfunction "1_1") (pintype "passive"))
      (node (ref "C90") (pin "1") (pinfunction "1_1") (pintype "passive"))
      (node (ref "C91") (pin "1") (pinfunction "1_1") (pintype "passive"))
      (node (ref "C92") (pin "1") (pinfunction "1_1") (pintype "passive"))
      (node (ref "C93") (pin "1") (pinfunction "1_1") (pintype "passive"))
      (node (ref "C94") (pin "1") (pinfunction "1_1") (pintype "passive"))
      (node (ref "C95") (pin "1") (pinfunction "1_1") (pintype "passive"))
      (node (ref "C96") (pin "1") (pinfunction "1_1") (pintype "passive"))
      (node (ref "C97") (pin "1") (pinfunction "1_1") (pintype "passive"))
      (node (ref "IC1") (pin "AH30") (pinfunction "DIGPRVDD2_AH30") (pintype "power_in"))
      (node (ref "IC1") (pin "H32") (pinfunction "DIGPRVDD2_H32") (pintype "power_in"))
      (node (ref "IC1") (pin "T32") (pinfunction "DIGPRVDD2_T32") (pintype "power_in"))
      (node (ref "IC1") (pin "W31") (pinfunction "DIGPRPOC_W31") (pintype "power_in"))
      (node (ref "IC1") (pin "W33") (pinfunction "DIGPRVDD2_W33") (pintype "power_in"))
      (node (ref "R69") (pin "2") (pinfunction "2_2") (pintype "passive"))
    )
    (net (code "7") (name "Net-(IC1E-VDD18_BIAS)") (class "Default")
      (node (ref "C101") (pin "1") (pinfunction "1_1") (pintype "passive"))
      (node (ref "FR30") (pin "1") (pinfunction "1_1") (pintype "passive"))
      (node (ref "IC1") (pin "E17") (pinfunction "VDD18_BIAS_E17") (pintype "power_in"))
    )
    (net (code "8") (name "Net-(IC1E-VDD18_DIG)") (class "Default")
      (node (ref "C87") (pin "1") (pinfunction "1_1") (pintype "passive"))
      (node (ref "IC1") (pin "D24") (pinfunction "VDD18_DIG_D24") (pintype "power_in"))
      (node (ref "R68") (pin "1") (pinfunction "1_1") (pintype "passive"))
    )
    (net (code "9") (name "Net-(IC1E-VDD18_LDO_RX)") (class "Default")
      (node (ref "C104") (pin "1") (pinfunction "1_1") (pintype "passive"))
      (node (ref "FR27") (pin "2") (pinfunction "2_2") (pintype "passive"))
      (node (ref "IC1") (pin "AE3") (pinfunction "VDD18_TIA_RFE_AE3") (pintype "power_in"))
      (node (ref "IC1") (pin "AF4") (pinfunction "VDD18_LDO_RX_AF4") (pintype "power_in"))
    )
    (net (code "10") (name "Net-(IC1E-VDD18_LDO_TX)") (class "Default")
      (node (ref "C105") (pin "1") (pinfunction "1_1") (pintype "passive"))
      (node (ref "FR26") (pin "2") (pinfunction "2_2") (pintype "passive"))
      (node (ref "IC1") (pin "N1") (pinfunction "VDD18_LDO_TX_N1") (pintype "power_in"))
    )
    (net (code "11") (name "Net-(IC1E-VDD18_RXBUF)") (class "Default")
      (node (ref "C106") (pin "1") (pinfunction "1_1") (pintype "passive"))
      (node (ref "FR34") (pin "1") (pinfunction "1_1") (pintype "passive"))
      (node (ref "IC1") (pin "AM26") (pinfunction "VDD18_RXBUF_AM26") (pintype "power_in"))
    )
    (net (code "12") (name "Net-(IC1E-VDD18_SXR)") (class "Default")
      (node (ref "C103") (pin "1") (pinfunction "1_1") (pintype "passive"))
      (node (ref "FR28") (pin "1") (pinfunction "1_1") (pintype "passive"))
      (node (ref "IC1") (pin "AM18") (pinfunction "VDD18_SXR_AM18") (pintype "power_in"))
    )
    (net (code "13") (name "Net-(IC1E-VDD18_TRF)") (class "Default")
      (node (ref "C100") (pin "1") (pinfunction "1_1") (pintype "passive"))
      (node (ref "FR31") (pin "1") (pinfunction "1_1") (pintype "passive"))
      (node (ref "IC1") (pin "D16") (pinfunction "VDD18_TRF_D16") (pintype "power_in"))
    )
    (net (code "14") (name "Net-(IC1E-VDD18_TXBUF)") (class "Default")
      (node (ref "C107") (pin "1") (pinfunction "1_1") (pintype "passive"))
      (node (ref "FR33") (pin "2") (pinfunction "2_2") (pintype "passive"))
      (node (ref "IC1") (pin "H6") (pinfunction "VDD18_TXBUF_H6") (pintype "power_in"))
    )
    (net (code "15") (name "Net-(IC1E-VDD18_VCO_CGEN)") (class "Default")
      (node (ref "C99") (pin "1") (pinfunction "1_1") (pintype "passive"))
      (node (ref "FR32") (pin "1") (pinfunction "1_1") (pintype "passive"))
      (node (ref "IC1") (pin "E21") (pinfunction "VDD18_VCO_CGEN_E21") (pintype "power_in"))
    )
    (net (code "16") (name "Net-(IC1E-VDD18_VCO_SXR)") (class "Default")
      (node (ref "C102") (pin "1") (pinfunction "1_1") (pintype "passive"))
      (node (ref "FR29") (pin "1") (pinfunction "1_1") (pintype "passive"))
      (node (ref "IC1") (pin "AK22") (pinfunction "VDD18_VCO_SXR_AK22") (pintype "power_in"))
    )
    (net (code "17") (name "Net-(IC1E-VDD18_VCO_SXT)") (class "Default")
      (node (ref "C98") (pin "1") (pinfunction "1_1") (pintype "passive"))
      (node (ref "FR25") (pin "1") (pinfunction "1_1") (pintype "passive"))
      (node (ref "IC1") (pin "G3") (pinfunction "VDD18_VCO_SXT_G3") (pintype "power_in"))
    )
    (net (code "18") (name "Net-(IC1F-DVDD_CGEN)") (class "Default")
      (node (ref "C52") (pin "1") (pinfunction "1_1") (pintype "passive"))
      (node (ref "C53") (pin "1") (pinfunction "1_1") (pintype "passive"))
      (node (ref "C54") (pin "1") (pinfunction "1_1") (pintype "passive"))
      (node (ref "FR6") (pin "1") (pinfunction "1_1") (pintype "passive"))
      (node (ref "IC1") (pin "A17") (pinfunction "DVDD_CGEN_A17") (pintype "power_in"))
      (node (ref "IC1") (pin "C25") (pinfunction "VDD12_DIG_C25") (pintype "power_in"))
      (node (ref "IC1") (pin "F24") (pinfunction "VDD_SPI_BUF_F24") (pintype "power_in"))
    )
    (net (code "19") (name "Net-(IC1F-DVDD_SXR)") (class "Default")
      (node (ref "C56") (pin "1") (pinfunction "1_1") (pintype "passive"))
      (node (ref "FR4") (pin "1") (pinfunction "1_1") (pintype "passive"))
      (node (ref "IC1") (pin "AL21") (pinfunction "DVDD_SXR_AL21") (pintype "power_in"))
    )
    (net (code "20") (name "Net-(IC1F-DVDD_SXT)") (class "Default")
      (node (ref "C55") (pin "2") (pinfunction "2_2") (pintype "passive"))
      (node (ref "FR5") (pin "1") (pinfunction "1_1") (pintype "passive"))
      (node (ref "IC1") (pin "M4") (pinfunction "DVDD_SXT_M4") (pintype "power_in"))
    )
    (net (code "21") (name "Net-(IC1F-VDD12O_VCO_SXT)") (class "Default")
      (node (ref "C78") (pin "2") (pinfunction "2_2") (pintype "passive"))
      (node (ref "FR7") (pin "1") (pinfunction "1_1") (pintype "passive"))
      (node (ref "IC1") (pin "J5") (pinfunction "VDD12O_VCO_SXT_J5") (pintype "power_in"))
      (node (ref "IC1") (pin "K6") (pinfunction "VDD12_VCO_SXT_K6") (pintype "power_in"))
    )
    (net (code "22") (name "Net-(IC1F-VDD12_LNA_RFE)") (class "Default")
      (node (ref "C75") (pin "1") (pinfunction "1_1") (pintype "passive"))
      (node (ref "FR11") (pin "1") (pinfunction "1_1") (pintype "passive"))
      (node (ref "IC1") (pin "AG5") (pinfunction "VDD12_LNA_RFE_AG5") (pintype "power_in"))
    )
    (net (code "23") (name "Net-(IC1F-VDD12_RXBUF)") (class "Default")
      (node (ref "C71") (pin "1") (pinfunction "1_1") (pintype "passive"))
      (node (ref "IC1") (pin "AP26") (pinfunction "VDD12_RXBUF_AP26") (pintype "power_in"))
      (node (ref "R67") (pin "1") (pinfunction "1_1") (pintype "passive"))
    )
    (net (code "24") (name "Net-(IC1F-VDD12_TIA_RFE)") (class "Default")
      (node (ref "C76") (pin "2") (pinfunction "2_2") (pintype "passive"))
      (node (ref "FR10") (pin "1") (pinfunction "1_1") (pintype "passive"))
      (node (ref "IC1") (pin "AD6") (pinfunction "VDD12_TIA_RFE_AD6") (pintype "power_in"))
    )
    (net (code "25") (name "Net-(IC1F-VDD12_TXBUF)") (class "Default")
      (node (ref "C63") (pin "1") (pinfunction "1_1") (pintype "passive"))
      (node (ref "IC1") (pin "G5") (pinfunction "VDD12_TXBUF_G5") (pintype "power_in"))
      (node (ref "R66") (pin "1") (pinfunction "1_1") (pintype "passive"))
    )
    (net (code "26") (name "Net-(IC1F-VDD12_VCO_SXR)") (class "Default")
      (node (ref "C72") (pin "1") (pinfunction "1_1") (pintype "passive"))
      (node (ref "FR14") (pin "1") (pinfunction "1_1") (pintype "passive"))
      (node (ref "IC1") (pin "AN23") (pinfunction "VDD12_VCO_SXR_AN23") (pintype "power_in"))
    )
    (net (code "27") (name "Net-(IC1F-VDD14_LNA_RFE)") (class "Default")
      (node (ref "C83") (pin "1") (pinfunction "1_1") (pintype "passive"))
      (node (ref "C84") (pin "1") (pinfunction "1_1") (pintype "passive"))
      (node (ref "C85") (pin "1") (pinfunction "1_1") (pintype "passive"))
      (node (ref "FR23") (pin "1") (pinfunction "1_1") (pintype "passive"))
      (node (ref "IC1") (pin "AD4") (pinfunction "VDD14_RBB_AD4") (pintype "power_in"))
      (node (ref "IC1") (pin "AF2") (pinfunction "VDD14_TIA_RFE_AF2") (pintype "power_in"))
      (node (ref "IC1") (pin "AF6") (pinfunction "VDD14_LNA_RFE_AF6") (pintype "power_in"))
    )
    (net (code "28") (name "Net-(IC1F-VDD14_VCO_CGEN)") (class "Default")
      (node (ref "C81") (pin "1") (pinfunction "1_1") (pintype "passive"))
      (node (ref "C82") (pin "1") (pinfunction "1_1") (pintype "passive"))
      (node (ref "FR24") (pin "1") (pinfunction "1_1") (pintype "passive"))
      (node (ref "IC1") (pin "C21") (pinfunction "VDD14_VCO_CGEN_C21") (pintype "power_in"))
    )
    (net (code "29") (name "Net-(IC1F-VDDO_DIV_SXT)") (class "Default")
      (node (ref "C80") (pin "1") (pinfunction "1_1") (pintype "passive"))
      (node (ref "FR21") (pin "1") (pinfunction "1_1") (pintype "passive"))
      (node (ref "IC1") (pin "K2") (pinfunction "VDDO_DIV_SXT_K2") (pintype "power_in"))
      (node (ref "IC1") (pin "L5") (pinfunction "VDD_DIV_SXT_L5") (pintype "power_in"))
    )
    (net (code "30") (name "Net-(IC1F-VDDO_TLOBUF_TRF)") (class "Default")
      (node (ref "C65") (pin "1") (pinfunction "1_1") (pintype "passive"))
      (node (ref "FR20") (pin "1") (pinfunction "1_1") (pintype "passive"))
      (node (ref "IC1") (pin "D6") (pinfunction "VDDO_TLOBUF_TRF_D6") (pintype "power_in"))
      (node (ref "IC1") (pin "F8") (pinfunction "VDD_TLOBUF_TRF_F8") (pintype "power_in"))
    )
    (net (code "31") (name "Net-(IC1F-VDD_AFE)") (class "Default")
      (node (ref "C70") (pin "1") (pinfunction "1_1") (pintype "passive"))
      (node (ref "FR16") (pin "1") (pinfunction "1_1") (pintype "passive"))
      (node (ref "IC1") (pin "AJ25") (pinfunction "VDD_AFE_AJ25") (pintype "power_in"))
    )
    (net (code "32") (name "Net-(IC1F-VDD_CP_CGEN)") (class "Default")
      (node (ref "C69") (pin "2") (pinfunction "2_2") (pintype "passive"))
      (node (ref "FR17") (pin "1") (pinfunction "1_1") (pintype "passive"))
      (node (ref "IC1") (pin "F20") (pinfunction "VDD_CP_CGEN_F20") (pintype "power_in"))
    )
    (net (code "33") (name "Net-(IC1F-VDD_CP_SXR)") (class "Default")
      (node (ref "C74") (pin "1") (pinfunction "1_1") (pintype "passive"))
      (node (ref "FR12") (pin "1") (pinfunction "1_1") (pintype "passive"))
      (node (ref "IC1") (pin "AL19") (pinfunction "VDD_CP_SXR_AL19") (pintype "power_in"))
    )
    (net (code "34") (name "Net-(IC1F-VDD_CP_SXT)") (class "Default")
      (node (ref "C77") (pin "1") (pinfunction "1_1") (pintype "passive"))
      (node (ref "FR8") (pin "1") (pinfunction "1_1") (pintype "passive"))
      (node (ref "IC1") (pin "J3") (pinfunction "VDD_CP_SXT_J3") (pintype "power_in"))
    )
    (net (code "35") (name "Net-(IC1F-VDD_DIV_CGEN)") (class "Default")
      (node (ref "C67") (pin "1") (pinfunction "1_1") (pintype "passive"))
      (node (ref "C68") (pin "1") (pinfunction "1_1") (pintype "passive"))
      (node (ref "FR18") (pin "1") (pinfunction "1_1") (pintype "passive"))
      (node (ref "IC1") (pin "E19") (pinfunction "VDD_DIV_CGEN_E19") (pintype "power_in"))
    )
    (net (code "36") (name "Net-(IC1F-VDD_DIV_SXR)") (class "Default")
      (node (ref "C73") (pin "1") (pinfunction "1_1") (pintype "passive"))
      (node (ref "FR13") (pin "1") (pinfunction "1_1") (pintype "passive"))
      (node (ref "IC1") (pin "AM20") (pinfunction "VDD_DIV_SXR_AM20") (pintype "power_in"))
    )
    (net (code "37") (name "Net-(IC1F-VDD_MXLOBUF_RFE)") (class "Default")
      (node (ref "C86") (pin "1") (pinfunction "1_1") (pintype "passive"))
      (node (ref "FR22") (pin "1") (pinfunction "1_1") (pintype "passive"))
      (node (ref "IC1") (pin "AN17") (pinfunction "VDD_MXLOBUF_RFE_AN17") (pintype "power_in"))
    )
    (net (code "38") (name "Net-(IC1F-VDD_TBB)") (class "Default")
      (node (ref "C64") (pin "1") (pinfunction "1_1") (pintype "passive"))
      (node (ref "FR9") (pin "1") (pinfunction "1_1") (pintype "passive"))
      (node (ref "IC1") (pin "P4") (pinfunction "VDD_TBB_P4") (pintype "power_in"))
    )
    (net (code "39") (name "Net-(IC1F-VDD_TPAD_TRF)") (class "Default")
      (node (ref "C66") (pin "1") (pinfunction "1_1") (pintype "passive"))
      (node (ref "FR19") (pin "1") (pinfunction "1_1") (pintype "passive"))
      (node (ref "IC1") (pin "B16") (pinfunction "VDD_TPAD_TRF_B16") (pintype "power_in"))
    )
    (net (code "40") (name "VCC1P4_LMS") (class "Default")
      (node (ref "FR21") (pin "2") (pinfunction "2_2") (pintype "passive"))
      (node (ref "FR22") (pin "2") (pinfunction "2_2") (pintype "passive"))
      (node (ref "FR23") (pin "2") (pinfunction "2_2") (pintype "passive"))
      (node (ref "FR24") (pin "2") (pinfunction "2_2") (pintype "passive"))
    )
    (net (code "41") (name "VCC1P8_LMS") (class "Default")
      (node (ref "FR25") (pin "2") (pinfunction "2_2") (pintype "passive"))
      (node (ref "FR26") (pin "1") (pinfunction "1_1") (pintype "passive"))
      (node (ref "FR27") (pin "1") (pinfunction "1_1") (pintype "passive"))
      (node (ref "FR28") (pin "2") (pinfunction "2_2") (pintype "passive"))
      (node (ref "FR29") (pin "2") (pinfunction "2_2") (pintype "passive"))
      (node (ref "FR30") (pin "2") (pinfunction "2_2") (pintype "passive"))
      (node (ref "FR31") (pin "2") (pinfunction "2_2") (pintype "passive"))
      (node (ref "FR32") (pin "2") (pinfunction "2_2") (pintype "passive"))
      (node (ref "R68") (pin "2") (pinfunction "2_2") (pintype "passive"))
      (node (ref "R70") (pin "2") (pinfunction "2_2") (pintype "passive"))
      (node (ref "R71") (pin "1") (pinfunction "1_1") (pintype "passive"))
    )
    (net (code "42") (name "VCC1P25_LMS") (class "Default")
      (node (ref "FR10") (pin "2") (pinfunction "2_2") (pintype "passive"))
      (node (ref "FR11") (pin "2") (pinfunction "2_2") (pintype "passive"))
      (node (ref "FR12") (pin "2") (pinfunction "2_2") (pintype "passive"))
      (node (ref "FR13") (pin "2") (pinfunction "2_2") (pintype "passive"))
      (node (ref "FR14") (pin "2") (pinfunction "2_2") (pintype "passive"))
      (node (ref "FR15") (pin "2") (pinfunction "2_2") (pintype "passive"))
      (node (ref "FR16") (pin "2") (pinfunction "2_2") (pintype "passive"))
      (node (ref "FR17") (pin "2") (pinfunction "2_2") (pintype "passive"))
      (node (ref "FR18") (pin "2") (pinfunction "2_2") (pintype "passive"))
      (node (ref "FR19") (pin "2") (pinfunction "2_2") (pintype "passive"))
      (node (ref "FR20") (pin "2") (pinfunction "2_2") (pintype "passive"))
      (node (ref "FR4") (pin "2") (pinfunction "2_2") (pintype "passive"))
      (node (ref "FR5") (pin "2") (pinfunction "2_2") (pintype "passive"))
      (node (ref "FR6") (pin "2") (pinfunction "2_2") (pintype "passive"))
      (node (ref "FR7") (pin "2") (pinfunction "2_2") (pintype "passive"))
      (node (ref "FR8") (pin "2") (pinfunction "2_2") (pintype "passive"))
      (node (ref "FR9") (pin "2") (pinfunction "2_2") (pintype "passive"))
      (node (ref "R65") (pin "1") (pinfunction "1_1") (pintype "passive"))
    )
    (net (code "43") (name "VDIO_LMS") (class "Default")
      (node (ref "R69") (pin "1") (pinfunction "1_1") (pintype "passive"))
    )
  )
)
